# MillingLight_48V.net
KiCad netlist of a schematic drawn in Altium Designer
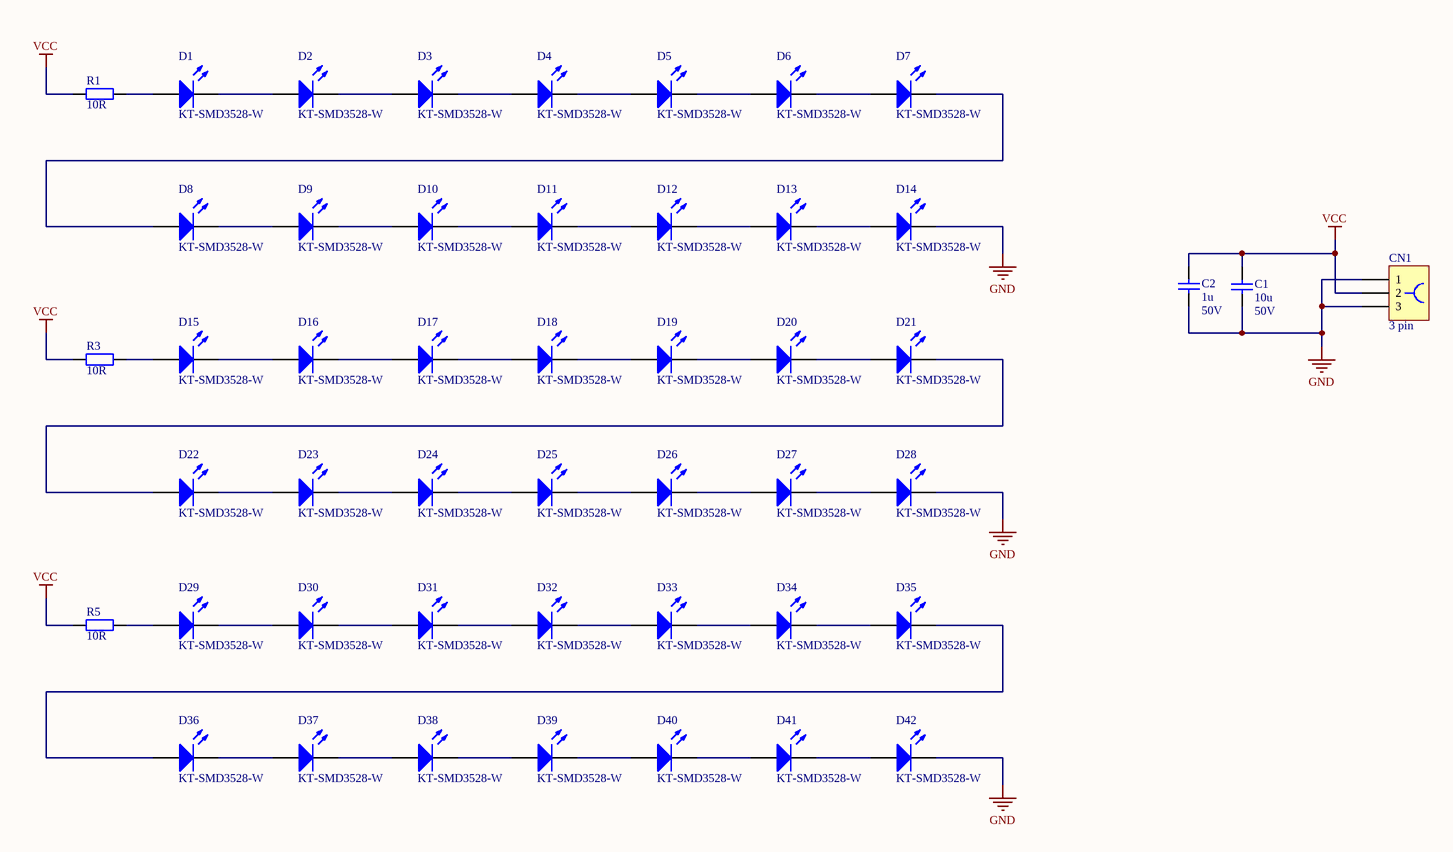
[diagram p0: MillingLight_48V.SchDoc]

(export (version "E")
  (design (tool "Eeschema 10.0.6"))
  (components
    (comp (ref "C1")
      (value "CAP")
      (footprint "CAPC3216X18N")
      (description "CAP, MLCC, X5R, 10UF, 50V, 1206")
      (fields
        (field (name "VALUE1") "10u")
        (field (name "VALUE2") "50V")
        (field (name "MANUFACTURER") "Murata")
      )
      (libsource (lib "DSW_Lib") (part "CAP"))
    )
    (comp (ref "C2")
      (value "CAP")
      (footprint "CAPC2012X125N")
      (description "X7R 10% 0805")
      (fields
        (field (name "VALUE1") "1u")
        (field (name "VALUE2") "50V")
        (field (name "MANUFACTURER") "KEMET")
      )
      (libsource (lib "DSW_Lib") (part "CAP"))
    )
    (comp (ref "CN1")
      (value "CN_1X3F")
      (footprint "CN_WURTH_691216510003")
      (description "WURTH ELEKTRONIK 691216510003 - T/BLOCK, 5,08mm 3W")
      (fields (field (name "VALUE1") "3 pin") (field (name "MANUFACTURER") "Wurth"))
      (libsource (lib "DSW_Lib") (part "CN_1X3F"))
    )
    (comp (ref "D1")
      (value "DIO_LED")
      (footprint "DIO_Kento_KT-SMD3528-W")
      (description "High Luminous PLCC2 Power Top SMD LED")
      (fields (field (name "VALUE1") "KT-SMD3528-W") (field (name "MANUFACTURER") "Kento"))
      (libsource (lib "DSW_Lib") (part "DIO_LED"))
    )
    (comp (ref "D2")
      (value "DIO_LED")
      (footprint "DIO_Kento_KT-SMD3528-W")
      (description "High Luminous PLCC2 Power Top SMD LED")
      (fields (field (name "VALUE1") "KT-SMD3528-W") (field (name "MANUFACTURER") "Kento"))
      (libsource (lib "DSW_Lib") (part "DIO_LED"))
    )
    (comp (ref "D3")
      (value "DIO_LED")
      (footprint "DIO_Kento_KT-SMD3528-W")
      (description "High Luminous PLCC2 Power Top SMD LED")
      (fields (field (name "VALUE1") "KT-SMD3528-W") (field (name "MANUFACTURER") "Kento"))
      (libsource (lib "DSW_Lib") (part "DIO_LED"))
    )
    (comp (ref "D4")
      (value "DIO_LED")
      (footprint "DIO_Kento_KT-SMD3528-W")
      (description "High Luminous PLCC2 Power Top SMD LED")
      (fields (field (name "VALUE1") "KT-SMD3528-W") (field (name "MANUFACTURER") "Kento"))
      (libsource (lib "DSW_Lib") (part "DIO_LED"))
    )
    (comp (ref "D5")
      (value "DIO_LED")
      (footprint "DIO_Kento_KT-SMD3528-W")
      (description "High Luminous PLCC2 Power Top SMD LED")
      (fields (field (name "VALUE1") "KT-SMD3528-W") (field (name "MANUFACTURER") "Kento"))
      (libsource (lib "DSW_Lib") (part "DIO_LED"))
    )
    (comp (ref "D6")
      (value "DIO_LED")
      (footprint "DIO_Kento_KT-SMD3528-W")
      (description "High Luminous PLCC2 Power Top SMD LED")
      (fields (field (name "VALUE1") "KT-SMD3528-W") (field (name "MANUFACTURER") "Kento"))
      (libsource (lib "DSW_Lib") (part "DIO_LED"))
    )
    (comp (ref "D7")
      (value "DIO_LED")
      (footprint "DIO_Kento_KT-SMD3528-W")
      (description "High Luminous PLCC2 Power Top SMD LED")
      (fields (field (name "VALUE1") "KT-SMD3528-W") (field (name "MANUFACTURER") "Kento"))
      (libsource (lib "DSW_Lib") (part "DIO_LED"))
    )
    (comp (ref "D8")
      (value "DIO_LED")
      (footprint "DIO_Kento_KT-SMD3528-W")
      (description "High Luminous PLCC2 Power Top SMD LED")
      (fields (field (name "VALUE1") "KT-SMD3528-W") (field (name "MANUFACTURER") "Kento"))
      (libsource (lib "DSW_Lib") (part "DIO_LED"))
    )
    (comp (ref "D9")
      (value "DIO_LED")
      (footprint "DIO_Kento_KT-SMD3528-W")
      (description "High Luminous PLCC2 Power Top SMD LED")
      (fields (field (name "VALUE1") "KT-SMD3528-W") (field (name "MANUFACTURER") "Kento"))
      (libsource (lib "DSW_Lib") (part "DIO_LED"))
    )
    (comp (ref "D10")
      (value "DIO_LED")
      (footprint "DIO_Kento_KT-SMD3528-W")
      (description "High Luminous PLCC2 Power Top SMD LED")
      (fields (field (name "VALUE1") "KT-SMD3528-W") (field (name "MANUFACTURER") "Kento"))
      (libsource (lib "DSW_Lib") (part "DIO_LED"))
    )
    (comp (ref "D11")
      (value "DIO_LED")
      (footprint "DIO_Kento_KT-SMD3528-W")
      (description "High Luminous PLCC2 Power Top SMD LED")
      (fields (field (name "VALUE1") "KT-SMD3528-W") (field (name "MANUFACTURER") "Kento"))
      (libsource (lib "DSW_Lib") (part "DIO_LED"))
    )
    (comp (ref "D12")
      (value "DIO_LED")
      (footprint "DIO_Kento_KT-SMD3528-W")
      (description "High Luminous PLCC2 Power Top SMD LED")
      (fields (field (name "VALUE1") "KT-SMD3528-W") (field (name "MANUFACTURER") "Kento"))
      (libsource (lib "DSW_Lib") (part "DIO_LED"))
    )
    (comp (ref "D13")
      (value "DIO_LED")
      (footprint "DIO_Kento_KT-SMD3528-W")
      (description "High Luminous PLCC2 Power Top SMD LED")
      (fields (field (name "VALUE1") "KT-SMD3528-W") (field (name "MANUFACTURER") "Kento"))
      (libsource (lib "DSW_Lib") (part "DIO_LED"))
    )
    (comp (ref "D14")
      (value "DIO_LED")
      (footprint "DIO_Kento_KT-SMD3528-W")
      (description "High Luminous PLCC2 Power Top SMD LED")
      (fields (field (name "VALUE1") "KT-SMD3528-W") (field (name "MANUFACTURER") "Kento"))
      (libsource (lib "DSW_Lib") (part "DIO_LED"))
    )
    (comp (ref "D15")
      (value "DIO_LED")
      (footprint "DIO_Kento_KT-SMD3528-W")
      (description "High Luminous PLCC2 Power Top SMD LED")
      (fields (field (name "VALUE1") "KT-SMD3528-W") (field (name "MANUFACTURER") "Kento"))
      (libsource (lib "DSW_Lib") (part "DIO_LED"))
    )
    (comp (ref "D16")
      (value "DIO_LED")
      (footprint "DIO_Kento_KT-SMD3528-W")
      (description "High Luminous PLCC2 Power Top SMD LED")
      (fields (field (name "VALUE1") "KT-SMD3528-W") (field (name "MANUFACTURER") "Kento"))
      (libsource (lib "DSW_Lib") (part "DIO_LED"))
    )
    (comp (ref "D17")
      (value "DIO_LED")
      (footprint "DIO_Kento_KT-SMD3528-W")
      (description "High Luminous PLCC2 Power Top SMD LED")
      (fields (field (name "VALUE1") "KT-SMD3528-W") (field (name "MANUFACTURER") "Kento"))
      (libsource (lib "DSW_Lib") (part "DIO_LED"))
    )
    (comp (ref "D18")
      (value "DIO_LED")
      (footprint "DIO_Kento_KT-SMD3528-W")
      (description "High Luminous PLCC2 Power Top SMD LED")
      (fields (field (name "VALUE1") "KT-SMD3528-W") (field (name "MANUFACTURER") "Kento"))
      (libsource (lib "DSW_Lib") (part "DIO_LED"))
    )
    (comp (ref "D19")
      (value "DIO_LED")
      (footprint "DIO_Kento_KT-SMD3528-W")
      (description "High Luminous PLCC2 Power Top SMD LED")
      (fields (field (name "VALUE1") "KT-SMD3528-W") (field (name "MANUFACTURER") "Kento"))
      (libsource (lib "DSW_Lib") (part "DIO_LED"))
    )
    (comp (ref "D20")
      (value "DIO_LED")
      (footprint "DIO_Kento_KT-SMD3528-W")
      (description "High Luminous PLCC2 Power Top SMD LED")
      (fields (field (name "VALUE1") "KT-SMD3528-W") (field (name "MANUFACTURER") "Kento"))
      (libsource (lib "DSW_Lib") (part "DIO_LED"))
    )
    (comp (ref "D21")
      (value "DIO_LED")
      (footprint "DIO_Kento_KT-SMD3528-W")
      (description "High Luminous PLCC2 Power Top SMD LED")
      (fields (field (name "VALUE1") "KT-SMD3528-W") (field (name "MANUFACTURER") "Kento"))
      (libsource (lib "DSW_Lib") (part "DIO_LED"))
    )
    (comp (ref "D22")
      (value "DIO_LED")
      (footprint "DIO_Kento_KT-SMD3528-W")
      (description "High Luminous PLCC2 Power Top SMD LED")
      (fields (field (name "VALUE1") "KT-SMD3528-W") (field (name "MANUFACTURER") "Kento"))
      (libsource (lib "DSW_Lib") (part "DIO_LED"))
    )
    (comp (ref "D23")
      (value "DIO_LED")
      (footprint "DIO_Kento_KT-SMD3528-W")
      (description "High Luminous PLCC2 Power Top SMD LED")
      (fields (field (name "VALUE1") "KT-SMD3528-W") (field (name "MANUFACTURER") "Kento"))
      (libsource (lib "DSW_Lib") (part "DIO_LED"))
    )
    (comp (ref "D24")
      (value "DIO_LED")
      (footprint "DIO_Kento_KT-SMD3528-W")
      (description "High Luminous PLCC2 Power Top SMD LED")
      (fields (field (name "VALUE1") "KT-SMD3528-W") (field (name "MANUFACTURER") "Kento"))
      (libsource (lib "DSW_Lib") (part "DIO_LED"))
    )
    (comp (ref "D25")
      (value "DIO_LED")
      (footprint "DIO_Kento_KT-SMD3528-W")
      (description "High Luminous PLCC2 Power Top SMD LED")
      (fields (field (name "VALUE1") "KT-SMD3528-W") (field (name "MANUFACTURER") "Kento"))
      (libsource (lib "DSW_Lib") (part "DIO_LED"))
    )
    (comp (ref "D26")
      (value "DIO_LED")
      (footprint "DIO_Kento_KT-SMD3528-W")
      (description "High Luminous PLCC2 Power Top SMD LED")
      (fields (field (name "VALUE1") "KT-SMD3528-W") (field (name "MANUFACTURER") "Kento"))
      (libsource (lib "DSW_Lib") (part "DIO_LED"))
    )
    (comp (ref "D27")
      (value "DIO_LED")
      (footprint "DIO_Kento_KT-SMD3528-W")
      (description "High Luminous PLCC2 Power Top SMD LED")
      (fields (field (name "VALUE1") "KT-SMD3528-W") (field (name "MANUFACTURER") "Kento"))
      (libsource (lib "DSW_Lib") (part "DIO_LED"))
    )
    (comp (ref "D28")
      (value "DIO_LED")
      (footprint "DIO_Kento_KT-SMD3528-W")
      (description "High Luminous PLCC2 Power Top SMD LED")
      (fields (field (name "VALUE1") "KT-SMD3528-W") (field (name "MANUFACTURER") "Kento"))
      (libsource (lib "DSW_Lib") (part "DIO_LED"))
    )
    (comp (ref "D29")
      (value "DIO_LED")
      (footprint "DIO_Kento_KT-SMD3528-W")
      (description "High Luminous PLCC2 Power Top SMD LED")
      (fields (field (name "VALUE1") "KT-SMD3528-W") (field (name "MANUFACTURER") "Kento"))
      (libsource (lib "DSW_Lib") (part "DIO_LED"))
    )
    (comp (ref "D30")
      (value "DIO_LED")
      (footprint "DIO_Kento_KT-SMD3528-W")
      (description "High Luminous PLCC2 Power Top SMD LED")
      (fields (field (name "VALUE1") "KT-SMD3528-W") (field (name "MANUFACTURER") "Kento"))
      (libsource (lib "DSW_Lib") (part "DIO_LED"))
    )
    (comp (ref "D31")
      (value "DIO_LED")
      (footprint "DIO_Kento_KT-SMD3528-W")
      (description "High Luminous PLCC2 Power Top SMD LED")
      (fields (field (name "VALUE1") "KT-SMD3528-W") (field (name "MANUFACTURER") "Kento"))
      (libsource (lib "DSW_Lib") (part "DIO_LED"))
    )
    (comp (ref "D32")
      (value "DIO_LED")
      (footprint "DIO_Kento_KT-SMD3528-W")
      (description "High Luminous PLCC2 Power Top SMD LED")
      (fields (field (name "VALUE1") "KT-SMD3528-W") (field (name "MANUFACTURER") "Kento"))
      (libsource (lib "DSW_Lib") (part "DIO_LED"))
    )
    (comp (ref "D33")
      (value "DIO_LED")
      (footprint "DIO_Kento_KT-SMD3528-W")
      (description "High Luminous PLCC2 Power Top SMD LED")
      (fields (field (name "VALUE1") "KT-SMD3528-W") (field (name "MANUFACTURER") "Kento"))
      (libsource (lib "DSW_Lib") (part "DIO_LED"))
    )
    (comp (ref "D34")
      (value "DIO_LED")
      (footprint "DIO_Kento_KT-SMD3528-W")
      (description "High Luminous PLCC2 Power Top SMD LED")
      (fields (field (name "VALUE1") "KT-SMD3528-W") (field (name "MANUFACTURER") "Kento"))
      (libsource (lib "DSW_Lib") (part "DIO_LED"))
    )
    (comp (ref "D35")
      (value "DIO_LED")
      (footprint "DIO_Kento_KT-SMD3528-W")
      (description "High Luminous PLCC2 Power Top SMD LED")
      (fields (field (name "VALUE1") "KT-SMD3528-W") (field (name "MANUFACTURER") "Kento"))
      (libsource (lib "DSW_Lib") (part "DIO_LED"))
    )
    (comp (ref "D36")
      (value "DIO_LED")
      (footprint "DIO_Kento_KT-SMD3528-W")
      (description "High Luminous PLCC2 Power Top SMD LED")
      (fields (field (name "VALUE1") "KT-SMD3528-W") (field (name "MANUFACTURER") "Kento"))
      (libsource (lib "DSW_Lib") (part "DIO_LED"))
    )
    (comp (ref "D37")
      (value "DIO_LED")
      (footprint "DIO_Kento_KT-SMD3528-W")
      (description "High Luminous PLCC2 Power Top SMD LED")
      (fields (field (name "VALUE1") "KT-SMD3528-W") (field (name "MANUFACTURER") "Kento"))
      (libsource (lib "DSW_Lib") (part "DIO_LED"))
    )
    (comp (ref "D38")
      (value "DIO_LED")
      (footprint "DIO_Kento_KT-SMD3528-W")
      (description "High Luminous PLCC2 Power Top SMD LED")
      (fields (field (name "VALUE1") "KT-SMD3528-W") (field (name "MANUFACTURER") "Kento"))
      (libsource (lib "DSW_Lib") (part "DIO_LED"))
    )
    (comp (ref "D39")
      (value "DIO_LED")
      (footprint "DIO_Kento_KT-SMD3528-W")
      (description "High Luminous PLCC2 Power Top SMD LED")
      (fields (field (name "VALUE1") "KT-SMD3528-W") (field (name "MANUFACTURER") "Kento"))
      (libsource (lib "DSW_Lib") (part "DIO_LED"))
    )
    (comp (ref "D40")
      (value "DIO_LED")
      (footprint "DIO_Kento_KT-SMD3528-W")
      (description "High Luminous PLCC2 Power Top SMD LED")
      (fields (field (name "VALUE1") "KT-SMD3528-W") (field (name "MANUFACTURER") "Kento"))
      (libsource (lib "DSW_Lib") (part "DIO_LED"))
    )
    (comp (ref "D41")
      (value "DIO_LED")
      (footprint "DIO_Kento_KT-SMD3528-W")
      (description "High Luminous PLCC2 Power Top SMD LED")
      (fields (field (name "VALUE1") "KT-SMD3528-W") (field (name "MANUFACTURER") "Kento"))
      (libsource (lib "DSW_Lib") (part "DIO_LED"))
    )
    (comp (ref "D42")
      (value "DIO_LED")
      (footprint "DIO_Kento_KT-SMD3528-W")
      (description "High Luminous PLCC2 Power Top SMD LED")
      (fields (field (name "VALUE1") "KT-SMD3528-W") (field (name "MANUFACTURER") "Kento"))
      (libsource (lib "DSW_Lib") (part "DIO_LED"))
    )
    (comp (ref "R1")
      (value "RES")
      (footprint "RESC2012X60N")
      (description "RESISTOR, 0805, 10R, 1%, SMD")
      (fields (field (name "VALUE1") "10R") (field (name "MANUFACTURER") "Yageo"))
      (libsource (lib "DSW_Lib") (part "RES"))
    )
    (comp (ref "R3")
      (value "RES")
      (footprint "RESC2012X60N")
      (description "RESISTOR, 0805, 10R, 1%, SMD")
      (fields (field (name "VALUE1") "10R") (field (name "MANUFACTURER") "Yageo"))
      (libsource (lib "DSW_Lib") (part "RES"))
    )
    (comp (ref "R5")
      (value "RES")
      (footprint "RESC2012X60N")
      (description "RESISTOR, 0805, 10R, 1%, SMD")
      (fields (field (name "VALUE1") "10R") (field (name "MANUFACTURER") "Yageo"))
      (libsource (lib "DSW_Lib") (part "RES"))
    )
  )
  (nets
    (net (code "1") (name "GND") (class "Default")
      (node (ref "C1") (pin "1") (pinfunction "1_1") (pintype "passive"))
      (node (ref "C2") (pin "1") (pinfunction "1_1") (pintype "passive"))
      (node (ref "CN1") (pin "1") (pinfunction "1_1") (pintype "passive"))
      (node (ref "CN1") (pin "3") (pinfunction "3_3") (pintype "passive"))
      (node (ref "D14") (pin "1") (pinfunction "K_1") (pintype "passive"))
      (node (ref "D28") (pin "1") (pinfunction "K_1") (pintype "passive"))
      (node (ref "D42") (pin "1") (pinfunction "K_1") (pintype "passive"))
    )
    (net (code "2") (name "Net-(D1-A)") (class "Default")
      (node (ref "D1") (pin "2") (pinfunction "A_2") (pintype "passive"))
      (node (ref "R1") (pin "2") (pinfunction "2_2") (pintype "passive"))
    )
    (net (code "3") (name "Net-(D1-K)") (class "Default")
      (node (ref "D1") (pin "1") (pinfunction "K_1") (pintype "passive"))
      (node (ref "D2") (pin "2") (pinfunction "A_2") (pintype "passive"))
    )
    (net (code "4") (name "Net-(D2-K)") (class "Default")
      (node (ref "D2") (pin "1") (pinfunction "K_1") (pintype "passive"))
      (node (ref "D3") (pin "2") (pinfunction "A_2") (pintype "passive"))
    )
    (net (code "5") (name "Net-(D3-K)") (class "Default")
      (node (ref "D3") (pin "1") (pinfunction "K_1") (pintype "passive"))
      (node (ref "D4") (pin "2") (pinfunction "A_2") (pintype "passive"))
    )
    (net (code "6") (name "Net-(D4-K)") (class "Default")
      (node (ref "D4") (pin "1") (pinfunction "K_1") (pintype "passive"))
      (node (ref "D5") (pin "2") (pinfunction "A_2") (pintype "passive"))
    )
    (net (code "7") (name "Net-(D5-K)") (class "Default")
      (node (ref "D5") (pin "1") (pinfunction "K_1") (pintype "passive"))
      (node (ref "D6") (pin "2") (pinfunction "A_2") (pintype "passive"))
    )
    (net (code "8") (name "Net-(D6-K)") (class "Default")
      (node (ref "D6") (pin "1") (pinfunction "K_1") (pintype "passive"))
      (node (ref "D7") (pin "2") (pinfunction "A_2") (pintype "passive"))
    )
    (net (code "9") (name "Net-(D7-K)") (class "Default")
      (node (ref "D7") (pin "1") (pinfunction "K_1") (pintype "passive"))
      (node (ref "D8") (pin "2") (pinfunction "A_2") (pintype "passive"))
    )
    (net (code "10") (name "Net-(D8-K)") (class "Default")
      (node (ref "D8") (pin "1") (pinfunction "K_1") (pintype "passive"))
      (node (ref "D9") (pin "2") (pinfunction "A_2") (pintype "passive"))
    )
    (net (code "11") (name "Net-(D10-A)") (class "Default")
      (node (ref "D10") (pin "2") (pinfunction "A_2") (pintype "passive"))
      (node (ref "D9") (pin "1") (pinfunction "K_1") (pintype "passive"))
    )
    (net (code "12") (name "Net-(D10-K)") (class "Default")
      (node (ref "D10") (pin "1") (pinfunction "K_1") (pintype "passive"))
      (node (ref "D11") (pin "2") (pinfunction "A_2") (pintype "passive"))
    )
    (net (code "13") (name "Net-(D11-K)") (class "Default")
      (node (ref "D11") (pin "1") (pinfunction "K_1") (pintype "passive"))
      (node (ref "D12") (pin "2") (pinfunction "A_2") (pintype "passive"))
    )
    (net (code "14") (name "Net-(D12-K)") (class "Default")
      (node (ref "D12") (pin "1") (pinfunction "K_1") (pintype "passive"))
      (node (ref "D13") (pin "2") (pinfunction "A_2") (pintype "passive"))
    )
    (net (code "15") (name "Net-(D13-K)") (class "Default")
      (node (ref "D13") (pin "1") (pinfunction "K_1") (pintype "passive"))
      (node (ref "D14") (pin "2") (pinfunction "A_2") (pintype "passive"))
    )
    (net (code "16") (name "Net-(D15-A)") (class "Default")
      (node (ref "D15") (pin "2") (pinfunction "A_2") (pintype "passive"))
      (node (ref "R3") (pin "2") (pinfunction "2_2") (pintype "passive"))
    )
    (net (code "17") (name "Net-(D15-K)") (class "Default")
      (node (ref "D15") (pin "1") (pinfunction "K_1") (pintype "passive"))
      (node (ref "D16") (pin "2") (pinfunction "A_2") (pintype "passive"))
    )
    (net (code "18") (name "Net-(D16-K)") (class "Default")
      (node (ref "D16") (pin "1") (pinfunction "K_1") (pintype "passive"))
      (node (ref "D17") (pin "2") (pinfunction "A_2") (pintype "passive"))
    )
    (net (code "19") (name "Net-(D17-K)") (class "Default")
      (node (ref "D17") (pin "1") (pinfunction "K_1") (pintype "passive"))
      (node (ref "D18") (pin "2") (pinfunction "A_2") (pintype "passive"))
    )
    (net (code "20") (name "Net-(D18-K)") (class "Default")
      (node (ref "D18") (pin "1") (pinfunction "K_1") (pintype "passive"))
      (node (ref "D19") (pin "2") (pinfunction "A_2") (pintype "passive"))
    )
    (net (code "21") (name "Net-(D19-K)") (class "Default")
      (node (ref "D19") (pin "1") (pinfunction "K_1") (pintype "passive"))
      (node (ref "D20") (pin "2") (pinfunction "A_2") (pintype "passive"))
    )
    (net (code "22") (name "Net-(D20-K)") (class "Default")
      (node (ref "D20") (pin "1") (pinfunction "K_1") (pintype "passive"))
      (node (ref "D21") (pin "2") (pinfunction "A_2") (pintype "passive"))
    )
    (net (code "23") (name "Net-(D21-K)") (class "Default")
      (node (ref "D21") (pin "1") (pinfunction "K_1") (pintype "passive"))
      (node (ref "D22") (pin "2") (pinfunction "A_2") (pintype "passive"))
    )
    (net (code "24") (name "Net-(D22-K)") (class "Default")
      (node (ref "D22") (pin "1") (pinfunction "K_1") (pintype "passive"))
      (node (ref "D23") (pin "2") (pinfunction "A_2") (pintype "passive"))
    )
    (net (code "25") (name "Net-(D23-K)") (class "Default")
      (node (ref "D23") (pin "1") (pinfunction "K_1") (pintype "passive"))
      (node (ref "D24") (pin "2") (pinfunction "A_2") (pintype "passive"))
    )
    (net (code "26") (name "Net-(D24-K)") (class "Default")
      (node (ref "D24") (pin "1") (pinfunction "K_1") (pintype "passive"))
      (node (ref "D25") (pin "2") (pinfunction "A_2") (pintype "passive"))
    )
    (net (code "27") (name "Net-(D25-K)") (class "Default")
      (node (ref "D25") (pin "1") (pinfunction "K_1") (pintype "passive"))
      (node (ref "D26") (pin "2") (pinfunction "A_2") (pintype "passive"))
    )
    (net (code "28") (name "Net-(D26-K)") (class "Default")
      (node (ref "D26") (pin "1") (pinfunction "K_1") (pintype "passive"))
      (node (ref "D27") (pin "2") (pinfunction "A_2") (pintype "passive"))
    )
    (net (code "29") (name "Net-(D27-K)") (class "Default")
      (node (ref "D27") (pin "1") (pinfunction "K_1") (pintype "passive"))
      (node (ref "D28") (pin "2") (pinfunction "A_2") (pintype "passive"))
    )
    (net (code "30") (name "Net-(D29-A)") (class "Default")
      (node (ref "D29") (pin "2") (pinfunction "A_2") (pintype "passive"))
      (node (ref "R5") (pin "2") (pinfunction "2_2") (pintype "passive"))
    )
    (net (code "31") (name "Net-(D29-K)") (class "Default")
      (node (ref "D29") (pin "1") (pinfunction "K_1") (pintype "passive"))
      (node (ref "D30") (pin "2") (pinfunction "A_2") (pintype "passive"))
    )
    (net (code "32") (name "Net-(D30-K)") (class "Default")
      (node (ref "D30") (pin "1") (pinfunction "K_1") (pintype "passive"))
      (node (ref "D31") (pin "2") (pinfunction "A_2") (pintype "passive"))
    )
    (net (code "33") (name "Net-(D31-K)") (class "Default")
      (node (ref "D31") (pin "1") (pinfunction "K_1") (pintype "passive"))
      (node (ref "D32") (pin "2") (pinfunction "A_2") (pintype "passive"))
    )
    (net (code "34") (name "Net-(D32-K)") (class "Default")
      (node (ref "D32") (pin "1") (pinfunction "K_1") (pintype "passive"))
      (node (ref "D33") (pin "2") (pinfunction "A_2") (pintype "passive"))
    )
    (net (code "35") (name "Net-(D33-K)") (class "Default")
      (node (ref "D33") (pin "1") (pinfunction "K_1") (pintype "passive"))
      (node (ref "D34") (pin "2") (pinfunction "A_2") (pintype "passive"))
    )
    (net (code "36") (name "Net-(D34-K)") (class "Default")
      (node (ref "D34") (pin "1") (pinfunction "K_1") (pintype "passive"))
      (node (ref "D35") (pin "2") (pinfunction "A_2") (pintype "passive"))
    )
    (net (code "37") (name "Net-(D35-K)") (class "Default")
      (node (ref "D35") (pin "1") (pinfunction "K_1") (pintype "passive"))
      (node (ref "D36") (pin "2") (pinfunction "A_2") (pintype "passive"))
    )
    (net (code "38") (name "Net-(D36-K)") (class "Default")
      (node (ref "D36") (pin "1") (pinfunction "K_1") (pintype "passive"))
      (node (ref "D37") (pin "2") (pinfunction "A_2") (pintype "passive"))
    )
    (net (code "39") (name "Net-(D37-K)") (class "Default")
      (node (ref "D37") (pin "1") (pinfunction "K_1") (pintype "passive"))
      (node (ref "D38") (pin "2") (pinfunction "A_2") (pintype "passive"))
    )
    (net (code "40") (name "Net-(D38-K)") (class "Default")
      (node (ref "D38") (pin "1") (pinfunction "K_1") (pintype "passive"))
      (node (ref "D39") (pin "2") (pinfunction "A_2") (pintype "passive"))
    )
    (net (code "41") (name "Net-(D39-K)") (class "Default")
      (node (ref "D39") (pin "1") (pinfunction "K_1") (pintype "passive"))
      (node (ref "D40") (pin "2") (pinfunction "A_2") (pintype "passive"))
    )
    (net (code "42") (name "Net-(D40-K)") (class "Default")
      (node (ref "D40") (pin "1") (pinfunction "K_1") (pintype "passive"))
      (node (ref "D41") (pin "2") (pinfunction "A_2") (pintype "passive"))
    )
    (net (code "43") (name "Net-(D41-K)") (class "Default")
      (node (ref "D41") (pin "1") (pinfunction "K_1") (pintype "passive"))
      (node (ref "D42") (pin "2") (pinfunction "A_2") (pintype "passive"))
    )
    (net (code "44") (name "VCC") (class "Default")
      (node (ref "C1") (pin "2") (pinfunction "2_2") (pintype "passive"))
      (node (ref "C2") (pin "2") (pinfunction "2_2") (pintype "passive"))
      (node (ref "CN1") (pin "2") (pinfunction "2_2") (pintype "passive"))
      (node (ref "R1") (pin "1") (pinfunction "1_1") (pintype "passive"))
      (node (ref "R3") (pin "1") (pinfunction "1_1") (pintype "passive"))
      (node (ref "R5") (pin "1") (pinfunction "1_1") (pintype "passive"))
    )
  )
)
